# stm32.net
KiCad netlist of a schematic drawn in Altium Designer
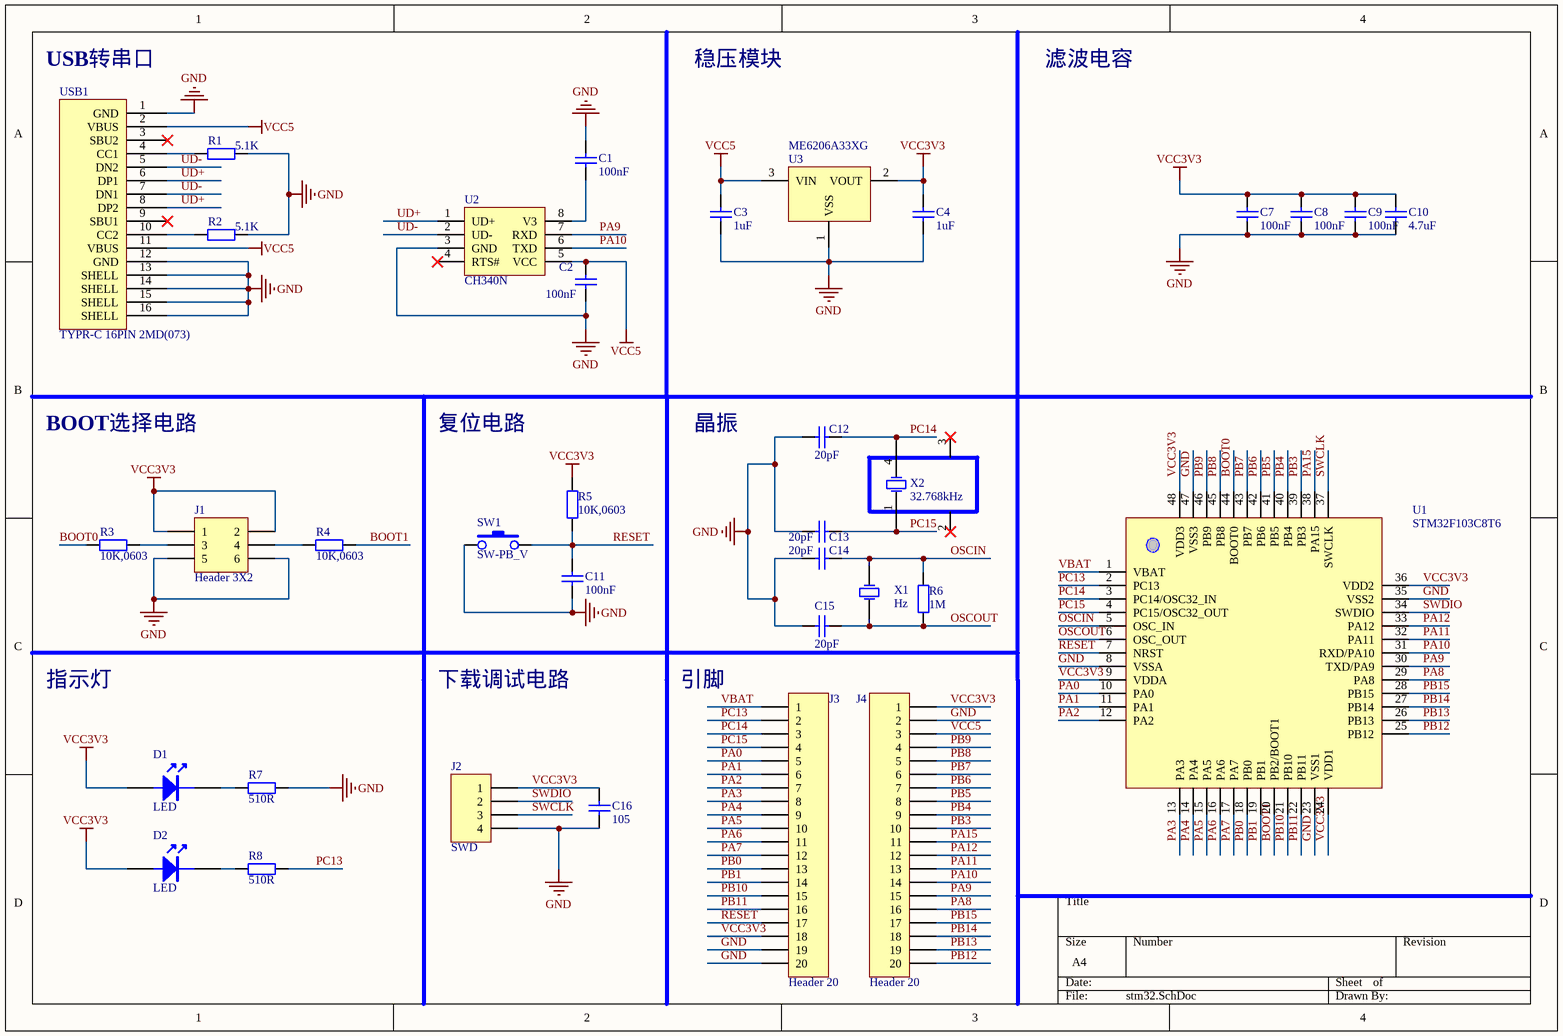
[diagram p0: stm32.SchDoc]

(export (version "E")
  (design (tool "Eeschema 10.0.6"))
  (components
    (comp (ref "C1")
      (value "100nF")
      (footprint "C0603")
      (description "Capacitor")
      (fields (field (name "PUBLISHER") "Altium Limited"))
      (libsource (lib "stm32") (part "Cap_1"))
    )
    (comp (ref "C2")
      (value "100nF")
      (footprint "C0603")
      (description "Capacitor")
      (fields (field (name "PUBLISHER") "Altium Limited"))
      (libsource (lib "stm32") (part "Cap_1"))
    )
    (comp (ref "C3")
      (value "1uF")
      (footprint "C0603")
      (description "Capacitor")
      (fields (field (name "PUBLISHER") "Altium Limited"))
      (libsource (lib "stm32") (part "Cap_1"))
    )
    (comp (ref "C4")
      (value "1uF")
      (footprint "C0603")
      (description "Capacitor")
      (fields (field (name "PUBLISHER") "Altium Limited"))
      (libsource (lib "stm32") (part "Cap_1"))
    )
    (comp (ref "C7")
      (value "100nF")
      (footprint "C0603")
      (description "Capacitor")
      (fields (field (name "PUBLISHER") "Altium Limited"))
      (libsource (lib "stm32") (part "Cap_1"))
    )
    (comp (ref "C8")
      (value "100nF")
      (footprint "C0603")
      (description "Capacitor")
      (fields (field (name "PUBLISHER") "Altium Limited"))
      (libsource (lib "stm32") (part "Cap_1"))
    )
    (comp (ref "C9")
      (value "100nF")
      (footprint "C0603")
      (description "Capacitor")
      (fields (field (name "PUBLISHER") "Altium Limited"))
      (libsource (lib "stm32") (part "Cap_1"))
    )
    (comp (ref "C10")
      (value "4.7uF")
      (footprint "C0603")
      (description "Capacitor")
      (fields (field (name "PUBLISHER") "Altium Limited"))
      (libsource (lib "stm32") (part "Cap_1"))
    )
    (comp (ref "C11")
      (value "100nF")
      (footprint "C0603")
      (description "Capacitor")
      (fields (field (name "PUBLISHER") "Altium Limited"))
      (libsource (lib "stm32") (part "Cap_1"))
    )
    (comp (ref "C12")
      (value "20pF")
      (footprint "C0603")
      (description "Capacitor")
      (fields (field (name "PUBLISHER") "Altium Limited"))
      (libsource (lib "stm32") (part "Cap_1"))
    )
    (comp (ref "C13")
      (value "20pF")
      (footprint "C0603")
      (description "Capacitor")
      (fields (field (name "PUBLISHER") "Altium Limited"))
      (libsource (lib "stm32") (part "Cap_1"))
    )
    (comp (ref "C14")
      (value "20pF")
      (footprint "C0603")
      (description "Capacitor")
      (fields (field (name "PUBLISHER") "Altium Limited"))
      (libsource (lib "stm32") (part "Cap_1"))
    )
    (comp (ref "C15")
      (value "20pF")
      (footprint "C0603")
      (description "Capacitor")
      (fields (field (name "PUBLISHER") "Altium Limited"))
      (libsource (lib "stm32") (part "Cap_1"))
    )
    (comp (ref "C16")
      (value "105")
      (footprint "C0603")
      (description "Capacitor")
      (fields (field (name "PUBLISHER") "Altium Limited"))
      (libsource (lib "stm32") (part "Cap_1"))
    )
    (comp (ref "D1") (value "LED") (footprint "LED") (libsource (lib "stm32") (part "LED_1")))
    (comp (ref "D2") (value "LED") (footprint "LED") (libsource (lib "stm32") (part "LED_1")))
    (comp (ref "J1")
      (value "Header 3X2")
      (footprint "HDR2X3")
      (description "Header, 3-Pin, Dual row")
      (fields (field (name "PUBLISHER") "Altium Limited"))
      (libsource (lib "stm32") (part "Header 3X2_1"))
    )
    (comp (ref "J2")
      (value "SWD")
      (footprint "HDR1X4H")
      (description "Header, 4-Pin")
      (fields (field (name "PUBLISHER") "Altium Limited"))
      (libsource (lib "stm32") (part "Header 4_1"))
    )
    (comp (ref "J3")
      (value "Header 20")
      (footprint "HDR1X20")
      (description "Header, 20-Pin")
      (fields (field (name "PUBLISHER") "Altium Limited"))
      (libsource (lib "stm32") (part "Header 20_1"))
    )
    (comp (ref "J4")
      (value "Header 20")
      (footprint "HDR1X20")
      (description "Header, 20-Pin")
      (fields (field (name "PUBLISHER") "Altium Limited"))
      (libsource (lib "") (part "Header 20_1_1"))
    )
    (comp (ref "R1")
      (value "5.1K")
      (footprint "R0603")
      (description "Resistor")
      (fields (field (name "PUBLISHER") "Altium Limited"))
      (libsource (lib "") (part "Res_1_1"))
    )
    (comp (ref "R2")
      (value "5.1K")
      (footprint "R0603")
      (description "Resistor")
      (fields (field (name "PUBLISHER") "Altium Limited"))
      (libsource (lib "") (part "Res_1_1"))
    )
    (comp (ref "R3")
      (value "10K,0603")
      (footprint "R0603")
      (description "Resistor")
      (fields (field (name "PUBLISHER") "Altium Limited"))
      (libsource (lib "stm32") (part "Res_1"))
    )
    (comp (ref "R4")
      (value "10K,0603")
      (footprint "R0603")
      (description "Resistor")
      (fields (field (name "PUBLISHER") "Altium Limited"))
      (libsource (lib "stm32") (part "Res_1"))
    )
    (comp (ref "R5")
      (value "10K,0603")
      (footprint "R0603")
      (description "Resistor")
      (fields (field (name "PUBLISHER") "Altium Limited"))
      (libsource (lib "") (part "Res_1_2"))
    )
    (comp (ref "R6")
      (value "1M")
      (footprint "R0603")
      (description "Resistor")
      (fields (field (name "PUBLISHER") "Altium Limited"))
      (libsource (lib "") (part "Res_1_2"))
    )
    (comp (ref "R7")
      (value "510R")
      (footprint "R0603")
      (description "Resistor  510Ω")
      (fields (field (name "PUBLISHER") "Altium Limited"))
      (libsource (lib "stm32") (part "Res_1"))
    )
    (comp (ref "R8")
      (value "510R")
      (footprint "R0603")
      (description "Resistor  510Ω")
      (fields (field (name "PUBLISHER") "Altium Limited"))
      (libsource (lib "stm32") (part "Res_1"))
    )
    (comp (ref "SW1")
      (value "SW-PB_V")
      (footprint "KET-SMT-2")
      (description "SWITCH")
      (libsource (lib "stm32") (part "SW-PB_V"))
    )
    (comp (ref "U1")
      (value "STM32F103C8T6")
      (footprint "48P")
      (libsource (lib "stm32") (part "STM32F103C8T6"))
    )
    (comp (ref "U2")
      (value "CH340N")
      (footprint "SOP_8(OPA)")
      (description "USB转串口芯片")
      (libsource (lib "stm32") (part "CH340N"))
    )
    (comp (ref "U3")
      (value "ME6206A33XG")
      (footprint "SOT-23-3")
      (description "3.3稳压")
      (libsource (lib "stm32") (part "ME6206A33XG"))
    )
    (comp (ref "USB1")
      (value "TYPR-C 16PIN 2MD(073)")
      (footprint "Type-C_USB")
      (description "TYPE-C-16PIN")
      (libsource (lib "stm32") (part "USB"))
    )
    (comp (ref "X1")
      (value "Hz")
      (footprint "XTAL1")
      (description "晶振")
      (libsource (lib "stm32") (part "XTAL"))
    )
    (comp (ref "X2")
      (value "32.768kHz")
      (footprint "MC-306")
      (description "晶振 32.768kHz")
      (libsource (lib "stm32") (part "XTAL_2"))
    )
  )
  (nets
    (net (code "1") (name "/BOOT0") (class "Default")
      (node (ref "R3") (pin "1") (pinfunction "1_1") (pintype "passive"))
      (node (ref "U1") (pin "44") (pinfunction "BOOT0_44") (pintype "passive"))
    )
    (net (code "2") (name "/BOOT1") (class "Default")
      (node (ref "R4") (pin "2") (pinfunction "2_2") (pintype "passive"))
      (node (ref "U1") (pin "20") (pinfunction "PB2/BOOT1_20") (pintype "passive"))
    )
    (net (code "3") (name "/OSCIN") (class "Default")
      (node (ref "C14") (pin "2") (pinfunction "2_2") (pintype "passive"))
      (node (ref "R6") (pin "2") (pinfunction "2_2") (pintype "passive"))
      (node (ref "U1") (pin "5") (pinfunction "OSC_IN_5") (pintype "passive"))
      (node (ref "X1") (pin "2") (pinfunction "2_2") (pintype "passive"))
    )
    (net (code "4") (name "/OSCOUT") (class "Default")
      (node (ref "C15") (pin "2") (pinfunction "2_2") (pintype "passive"))
      (node (ref "R6") (pin "1") (pinfunction "1_1") (pintype "passive"))
      (node (ref "U1") (pin "6") (pinfunction "OSC_OUT_6") (pintype "passive"))
      (node (ref "X1") (pin "1") (pinfunction "1_1") (pintype "passive"))
    )
    (net (code "5") (name "/PA0") (class "Default")
      (node (ref "J3") (pin "5") (pinfunction "5_5") (pintype "passive"))
      (node (ref "U1") (pin "10") (pinfunction "PA0_10") (pintype "passive"))
    )
    (net (code "6") (name "/PA1") (class "Default")
      (node (ref "J3") (pin "6") (pinfunction "6_6") (pintype "passive"))
      (node (ref "U1") (pin "11") (pinfunction "PA1_11") (pintype "passive"))
    )
    (net (code "7") (name "/PA2") (class "Default")
      (node (ref "J3") (pin "7") (pinfunction "7_7") (pintype "passive"))
      (node (ref "U1") (pin "12") (pinfunction "PA2_12") (pintype "passive"))
    )
    (net (code "8") (name "/PA3") (class "Default")
      (node (ref "J3") (pin "8") (pinfunction "8_8") (pintype "passive"))
      (node (ref "U1") (pin "13") (pinfunction "PA3_13") (pintype "passive"))
    )
    (net (code "9") (name "/PA4") (class "Default")
      (node (ref "J3") (pin "9") (pinfunction "9_9") (pintype "passive"))
      (node (ref "U1") (pin "14") (pinfunction "PA4_14") (pintype "passive"))
    )
    (net (code "10") (name "/PA5") (class "Default")
      (node (ref "J3") (pin "10") (pinfunction "10_10") (pintype "passive"))
      (node (ref "U1") (pin "15") (pinfunction "PA5_15") (pintype "passive"))
    )
    (net (code "11") (name "/PA6") (class "Default")
      (node (ref "J3") (pin "11") (pinfunction "11_11") (pintype "passive"))
      (node (ref "U1") (pin "16") (pinfunction "PA6_16") (pintype "passive"))
    )
    (net (code "12") (name "/PA7") (class "Default")
      (node (ref "J3") (pin "12") (pinfunction "12_12") (pintype "passive"))
      (node (ref "U1") (pin "17") (pinfunction "PA7_17") (pintype "passive"))
    )
    (net (code "13") (name "/PA8") (class "Default")
      (node (ref "J4") (pin "16") (pinfunction "16_16") (pintype "passive"))
      (node (ref "U1") (pin "29") (pinfunction "PA8_29") (pintype "passive"))
    )
    (net (code "14") (name "/PA9") (class "Default")
      (node (ref "J4") (pin "15") (pinfunction "15_15") (pintype "passive"))
      (node (ref "U1") (pin "30") (pinfunction "TXD/PA9_30") (pintype "passive"))
      (node (ref "U2") (pin "7") (pinfunction "RXD_7") (pintype "passive"))
    )
    (net (code "15") (name "/PA10") (class "Default")
      (node (ref "J4") (pin "14") (pinfunction "14_14") (pintype "passive"))
      (node (ref "U1") (pin "31") (pinfunction "RXD/PA10_31") (pintype "passive"))
      (node (ref "U2") (pin "6") (pinfunction "TXD_6") (pintype "passive"))
    )
    (net (code "16") (name "/PA11") (class "Default")
      (node (ref "J4") (pin "13") (pinfunction "13_13") (pintype "passive"))
      (node (ref "U1") (pin "32") (pinfunction "PA11_32") (pintype "passive"))
    )
    (net (code "17") (name "/PA12") (class "Default")
      (node (ref "J4") (pin "12") (pinfunction "12_12") (pintype "passive"))
      (node (ref "U1") (pin "33") (pinfunction "PA12_33") (pintype "passive"))
    )
    (net (code "18") (name "/PA15") (class "Default")
      (node (ref "J4") (pin "11") (pinfunction "11_11") (pintype "passive"))
      (node (ref "U1") (pin "38") (pinfunction "PA15_38") (pintype "passive"))
    )
    (net (code "19") (name "/PB0") (class "Default")
      (node (ref "J3") (pin "13") (pinfunction "13_13") (pintype "passive"))
      (node (ref "U1") (pin "18") (pinfunction "PB0_18") (pintype "passive"))
    )
    (net (code "20") (name "/PB1") (class "Default")
      (node (ref "J3") (pin "14") (pinfunction "14_14") (pintype "passive"))
      (node (ref "U1") (pin "19") (pinfunction "PB1_19") (pintype "passive"))
    )
    (net (code "21") (name "/PB3") (class "Default")
      (node (ref "J4") (pin "10") (pinfunction "10_10") (pintype "passive"))
      (node (ref "U1") (pin "39") (pinfunction "PB3_39") (pintype "passive"))
    )
    (net (code "22") (name "/PB4") (class "Default")
      (node (ref "J4") (pin "9") (pinfunction "9_9") (pintype "passive"))
      (node (ref "U1") (pin "40") (pinfunction "PB4_40") (pintype "passive"))
    )
    (net (code "23") (name "/PB5") (class "Default")
      (node (ref "J4") (pin "8") (pinfunction "8_8") (pintype "passive"))
      (node (ref "U1") (pin "41") (pinfunction "PB5_41") (pintype "passive"))
    )
    (net (code "24") (name "/PB6") (class "Default")
      (node (ref "J4") (pin "7") (pinfunction "7_7") (pintype "passive"))
      (node (ref "U1") (pin "42") (pinfunction "PB6_42") (pintype "passive"))
    )
    (net (code "25") (name "/PB7") (class "Default")
      (node (ref "J4") (pin "6") (pinfunction "6_6") (pintype "passive"))
      (node (ref "U1") (pin "43") (pinfunction "PB7_43") (pintype "passive"))
    )
    (net (code "26") (name "/PB8") (class "Default")
      (node (ref "J4") (pin "5") (pinfunction "5_5") (pintype "passive"))
      (node (ref "U1") (pin "45") (pinfunction "PB8_45") (pintype "passive"))
    )
    (net (code "27") (name "/PB9") (class "Default")
      (node (ref "J4") (pin "4") (pinfunction "4_4") (pintype "passive"))
      (node (ref "U1") (pin "46") (pinfunction "PB9_46") (pintype "passive"))
    )
    (net (code "28") (name "/PB10") (class "Default")
      (node (ref "J3") (pin "15") (pinfunction "15_15") (pintype "passive"))
      (node (ref "U1") (pin "21") (pinfunction "PB10_21") (pintype "passive"))
    )
    (net (code "29") (name "/PB11") (class "Default")
      (node (ref "J3") (pin "16") (pinfunction "16_16") (pintype "passive"))
      (node (ref "U1") (pin "22") (pinfunction "PB11_22") (pintype "passive"))
    )
    (net (code "30") (name "/PB12") (class "Default")
      (node (ref "J4") (pin "20") (pinfunction "20_20") (pintype "passive"))
      (node (ref "U1") (pin "25") (pinfunction "PB12_25") (pintype "passive"))
    )
    (net (code "31") (name "/PB13") (class "Default")
      (node (ref "J4") (pin "19") (pinfunction "19_19") (pintype "passive"))
      (node (ref "U1") (pin "26") (pinfunction "PB13_26") (pintype "passive"))
    )
    (net (code "32") (name "/PB14") (class "Default")
      (node (ref "J4") (pin "18") (pinfunction "18_18") (pintype "passive"))
      (node (ref "U1") (pin "27") (pinfunction "PB14_27") (pintype "passive"))
    )
    (net (code "33") (name "/PB15") (class "Default")
      (node (ref "J4") (pin "17") (pinfunction "17_17") (pintype "passive"))
      (node (ref "U1") (pin "28") (pinfunction "PB15_28") (pintype "passive"))
    )
    (net (code "34") (name "/PC13") (class "Default")
      (node (ref "J3") (pin "2") (pinfunction "2_2") (pintype "passive"))
      (node (ref "R8") (pin "2") (pinfunction "2_2") (pintype "passive"))
      (node (ref "U1") (pin "2") (pinfunction "PC13_2") (pintype "passive"))
    )
    (net (code "35") (name "/PC14") (class "Default")
      (node (ref "C12") (pin "2") (pinfunction "2_2") (pintype "passive"))
      (node (ref "J3") (pin "3") (pinfunction "3_3") (pintype "passive"))
      (node (ref "U1") (pin "3") (pinfunction "PC14/OSC32_IN_3") (pintype "passive"))
      (node (ref "X2") (pin "4") (pinfunction "4_4") (pintype "passive"))
    )
    (net (code "36") (name "/PC15") (class "Default")
      (node (ref "C13") (pin "2") (pinfunction "2_2") (pintype "passive"))
      (node (ref "J3") (pin "4") (pinfunction "4_4") (pintype "passive"))
      (node (ref "U1") (pin "4") (pinfunction "PC15/OSC32_OUT_4") (pintype "passive"))
      (node (ref "X2") (pin "1") (pinfunction "1_1") (pintype "passive"))
    )
    (net (code "37") (name "/RESET") (class "Default")
      (node (ref "C11") (pin "2") (pinfunction "2_2") (pintype "passive"))
      (node (ref "J3") (pin "17") (pinfunction "17_17") (pintype "passive"))
      (node (ref "R5") (pin "1") (pinfunction "1_1") (pintype "passive"))
      (node (ref "SW1") (pin "2") (pinfunction "2_2") (pintype "passive"))
      (node (ref "U1") (pin "7") (pinfunction "NRST_7") (pintype "passive"))
    )
    (net (code "38") (name "/SWCLK") (class "Default")
      (node (ref "J2") (pin "3") (pinfunction "3_3") (pintype "passive"))
      (node (ref "U1") (pin "37") (pinfunction "SWCLK_37") (pintype "passive"))
    )
    (net (code "39") (name "/SWDIO") (class "Default")
      (node (ref "J2") (pin "2") (pinfunction "2_2") (pintype "passive"))
      (node (ref "U1") (pin "34") (pinfunction "SWDIO_34") (pintype "passive"))
    )
    (net (code "40") (name "/UD+") (class "Default")
      (node (ref "U2") (pin "1") (pinfunction "UD+_1") (pintype "passive"))
      (node (ref "USB1") (pin "6") (pinfunction "DP1_6") (pintype "passive"))
      (node (ref "USB1") (pin "8") (pinfunction "DP2_8") (pintype "passive"))
    )
    (net (code "41") (name "/UD-") (class "Default")
      (node (ref "U2") (pin "2") (pinfunction "UD-_2") (pintype "passive"))
      (node (ref "USB1") (pin "5") (pinfunction "DN2_5") (pintype "passive"))
      (node (ref "USB1") (pin "7") (pinfunction "DN1_7") (pintype "passive"))
    )
    (net (code "42") (name "/VBAT") (class "Default")
      (node (ref "J3") (pin "1") (pinfunction "1_1") (pintype "passive"))
      (node (ref "U1") (pin "1") (pinfunction "VBAT_1") (pintype "passive"))
    )
    (net (code "43") (name "GND") (class "Default")
      (node (ref "C1") (pin "1") (pinfunction "1_1") (pintype "passive"))
      (node (ref "C10") (pin "2") (pinfunction "2_2") (pintype "passive"))
      (node (ref "C11") (pin "1") (pinfunction "1_1") (pintype "passive"))
      (node (ref "C12") (pin "1") (pinfunction "1_1") (pintype "passive"))
      (node (ref "C13") (pin "1") (pinfunction "1_1") (pintype "passive"))
      (node (ref "C14") (pin "1") (pinfunction "1_1") (pintype "passive"))
      (node (ref "C15") (pin "1") (pinfunction "1_1") (pintype "passive"))
      (node (ref "C16") (pin "1") (pinfunction "1_1") (pintype "passive"))
      (node (ref "C2") (pin "1") (pinfunction "1_1") (pintype "passive"))
      (node (ref "C3") (pin "1") (pinfunction "1_1") (pintype "passive"))
      (node (ref "C4") (pin "1") (pinfunction "1_1") (pintype "passive"))
      (node (ref "C7") (pin "2") (pinfunction "2_2") (pintype "passive"))
      (node (ref "C8") (pin "2") (pinfunction "2_2") (pintype "passive"))
      (node (ref "C9") (pin "2") (pinfunction "2_2") (pintype "passive"))
      (node (ref "J1") (pin "5") (pinfunction "5_5") (pintype "passive"))
      (node (ref "J1") (pin "6") (pinfunction "6_6") (pintype "passive"))
      (node (ref "J2") (pin "4") (pinfunction "4_4") (pintype "passive"))
      (node (ref "J3") (pin "19") (pinfunction "19_19") (pintype "passive"))
      (node (ref "J3") (pin "20") (pinfunction "20_20") (pintype "passive"))
      (node (ref "J4") (pin "2") (pinfunction "2_2") (pintype "passive"))
      (node (ref "R1") (pin "1") (pinfunction "1_1") (pintype "passive"))
      (node (ref "R2") (pin "1") (pinfunction "1_1") (pintype "passive"))
      (node (ref "R7") (pin "2") (pinfunction "2_2") (pintype "passive"))
      (node (ref "SW1") (pin "1") (pinfunction "1_1") (pintype "passive"))
      (node (ref "U1") (pin "23") (pinfunction "VSS1_23") (pintype "passive"))
      (node (ref "U1") (pin "35") (pinfunction "VSS2_35") (pintype "passive"))
      (node (ref "U1") (pin "47") (pinfunction "VSS3_47") (pintype "passive"))
      (node (ref "U1") (pin "8") (pinfunction "VSSA_8") (pintype "passive"))
      (node (ref "U2") (pin "3") (pinfunction "GND_3") (pintype "passive"))
      (node (ref "U3") (pin "1") (pinfunction "VSS_1") (pintype "passive"))
      (node (ref "USB1") (pin "1") (pinfunction "GND_1") (pintype "passive"))
      (node (ref "USB1") (pin "12") (pinfunction "GND_12") (pintype "passive"))
      (node (ref "USB1") (pin "13") (pinfunction "SHELL_13") (pintype "passive"))
      (node (ref "USB1") (pin "14") (pinfunction "SHELL_14") (pintype "passive"))
      (node (ref "USB1") (pin "15") (pinfunction "SHELL_15") (pintype "passive"))
      (node (ref "USB1") (pin "16") (pinfunction "SHELL_16") (pintype "passive"))
    )
    (net (code "44") (name "Net-(D1-2)") (class "Default")
      (node (ref "D1") (pin "K") (pinfunction "2_K") (pintype "passive"))
      (node (ref "R7") (pin "1") (pinfunction "1_1") (pintype "passive"))
    )
    (net (code "45") (name "Net-(D2-2)") (class "Default")
      (node (ref "D2") (pin "K") (pinfunction "2_K") (pintype "passive"))
      (node (ref "R8") (pin "1") (pinfunction "1_1") (pintype "passive"))
    )
    (net (code "46") (name "Net-(J1-Pad3)") (class "Default")
      (node (ref "J1") (pin "3") (pinfunction "3_3") (pintype "passive"))
      (node (ref "R3") (pin "2") (pinfunction "2_2") (pintype "passive"))
    )
    (net (code "47") (name "Net-(J1-Pad4)") (class "Default")
      (node (ref "J1") (pin "4") (pinfunction "4_4") (pintype "passive"))
      (node (ref "R4") (pin "1") (pinfunction "1_1") (pintype "passive"))
    )
    (net (code "48") (name "Net-(U2-V3)") (class "Default")
      (node (ref "C1") (pin "2") (pinfunction "2_2") (pintype "passive"))
      (node (ref "U2") (pin "8") (pinfunction "V3_8") (pintype "passive"))
    )
    (net (code "49") (name "Net-(USB1-CC1)") (class "Default")
      (node (ref "R1") (pin "2") (pinfunction "2_2") (pintype "passive"))
      (node (ref "USB1") (pin "4") (pinfunction "CC1_4") (pintype "passive"))
    )
    (net (code "50") (name "Net-(USB1-CC2)") (class "Default")
      (node (ref "R2") (pin "2") (pinfunction "2_2") (pintype "passive"))
      (node (ref "USB1") (pin "10") (pinfunction "CC2_10") (pintype "passive"))
    )
    (net (code "51") (name "VCC3V3") (class "Default")
      (node (ref "C10") (pin "1") (pinfunction "1_1") (pintype "passive"))
      (node (ref "C16") (pin "2") (pinfunction "2_2") (pintype "passive"))
      (node (ref "C4") (pin "2") (pinfunction "2_2") (pintype "passive"))
      (node (ref "C7") (pin "1") (pinfunction "1_1") (pintype "passive"))
      (node (ref "C8") (pin "1") (pinfunction "1_1") (pintype "passive"))
      (node (ref "C9") (pin "1") (pinfunction "1_1") (pintype "passive"))
      (node (ref "D1") (pin "A") (pinfunction "1_A") (pintype "passive"))
      (node (ref "D2") (pin "A") (pinfunction "1_A") (pintype "passive"))
      (node (ref "J1") (pin "1") (pinfunction "1_1") (pintype "passive"))
      (node (ref "J1") (pin "2") (pinfunction "2_2") (pintype "passive"))
      (node (ref "J2") (pin "1") (pinfunction "1_1") (pintype "passive"))
      (node (ref "J3") (pin "18") (pinfunction "18_18") (pintype "passive"))
      (node (ref "J4") (pin "1") (pinfunction "1_1") (pintype "passive"))
      (node (ref "R5") (pin "2") (pinfunction "2_2") (pintype "passive"))
      (node (ref "U1") (pin "24") (pinfunction "VDD1_24") (pintype "passive"))
      (node (ref "U1") (pin "36") (pinfunction "VDD2_36") (pintype "passive"))
      (node (ref "U1") (pin "48") (pinfunction "VDD3_48") (pintype "passive"))
      (node (ref "U1") (pin "9") (pinfunction "VDDA_9") (pintype "passive"))
      (node (ref "U3") (pin "2") (pinfunction "VOUT_2") (pintype "passive"))
    )
    (net (code "52") (name "VCC5") (class "Default")
      (node (ref "C2") (pin "2") (pinfunction "2_2") (pintype "passive"))
      (node (ref "C3") (pin "2") (pinfunction "2_2") (pintype "passive"))
      (node (ref "J4") (pin "3") (pinfunction "3_3") (pintype "passive"))
      (node (ref "U2") (pin "5") (pinfunction "VCC_5") (pintype "passive"))
      (node (ref "U3") (pin "3") (pinfunction "VIN_3") (pintype "passive"))
      (node (ref "USB1") (pin "11") (pinfunction "VBUS_11") (pintype "passive"))
      (node (ref "USB1") (pin "2") (pinfunction "VBUS_2") (pintype "passive"))
    )
    (net (code "53") (name "unconnected-(U2-RTS#-Pad4)") (class "Default")
      (node (ref "U2") (pin "4") (pinfunction "RTS#_4") (pintype "passive+no_connect"))
    )
    (net (code "54") (name "unconnected-(USB1-SBU1-Pad9)") (class "Default")
      (node (ref "USB1") (pin "9") (pinfunction "SBU1_9") (pintype "passive+no_connect"))
    )
    (net (code "55") (name "unconnected-(USB1-SBU2-Pad3)") (class "Default")
      (node (ref "USB1") (pin "3") (pinfunction "SBU2_3") (pintype "passive+no_connect"))
    )
    (net (code "56") (name "unconnected-(X2-Pad2)") (class "Default")
      (node (ref "X2") (pin "2") (pinfunction "2_2") (pintype "passive+no_connect"))
    )
    (net (code "57") (name "unconnected-(X2-Pad3)") (class "Default")
      (node (ref "X2") (pin "3") (pinfunction "3_3") (pintype "passive+no_connect"))
    )
  )
)
